# ATTiny85Shield.net
KiCad netlist of a schematic drawn in EAGLE
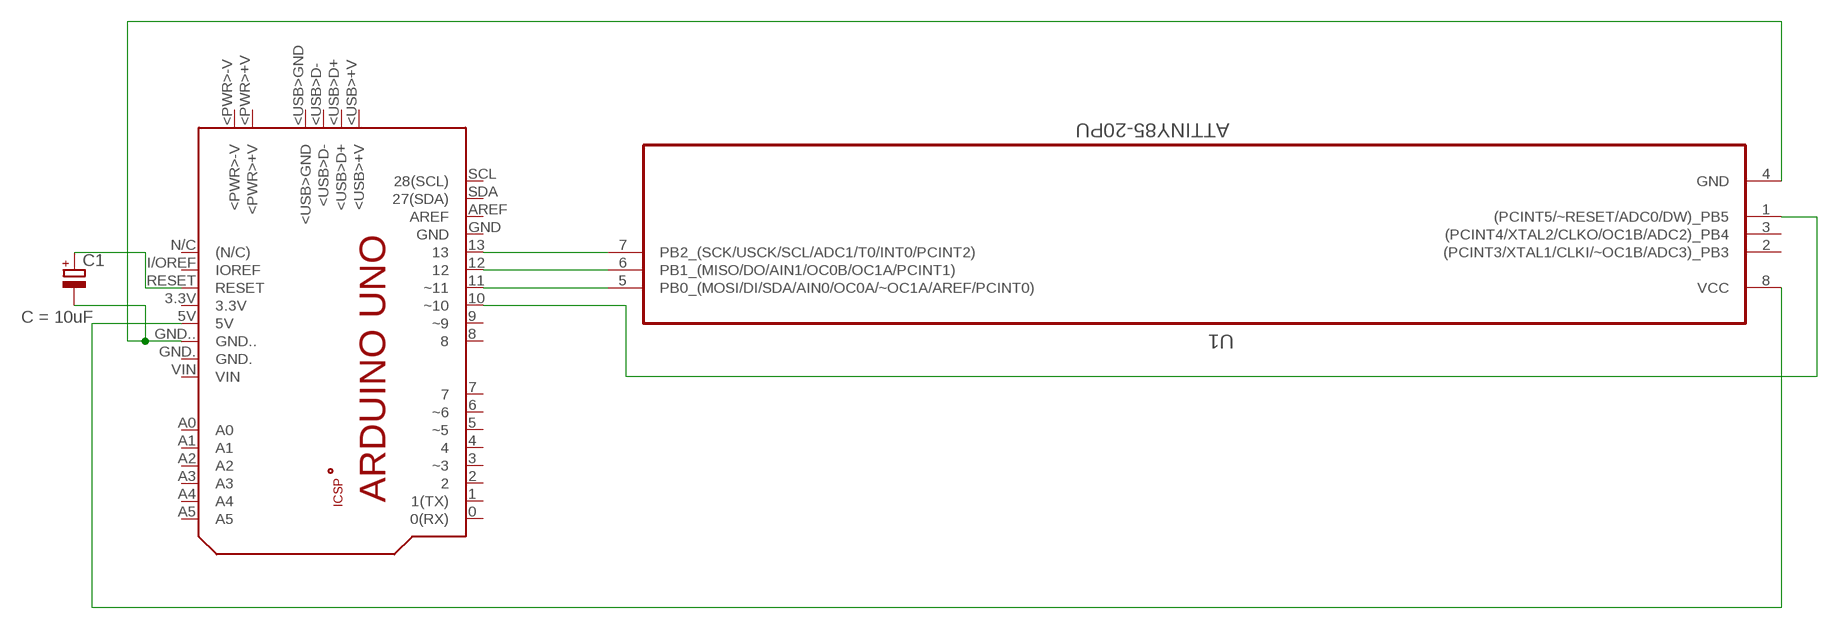
[diagram p0: schematic, sheet 1]

(export (version "E")
  (design (tool "Eeschema 10.0.6"))
  (components
    (comp (ref "C1")
      (value "CPOL-EUE3.5-8")
      (footprint "eagle-import:E3,5-8")
      (fields (field (name "C") "10uF"))
      (libsource (lib "eagle-import") (part "CPOL-EUE3.5-8"))
    )
    (comp (ref "PCB1")
      (value "ARDUINO_UNO")
      (footprint "eagle-import:ARDUINO_UNO")
      (libsource (lib "eagle-import") (part "ARDUINO_UNO"))
    )
    (comp (ref "U1")
      (value "ATTINY85-20PU")
      (footprint "eagle-import:DIP254P762X533-8")
      (libsource (lib "eagle-import") (part "ATTINY85-20PU"))
    )
  )
  (nets
    (net (code "1") (name "Net-(C1-Pad+)") (class "Default")
      (node (ref "C1") (pin "+") (pinfunction "+_+") (pintype "passive"))
      (node (ref "PCB1") (pin "RESET") (pinfunction "RESET_RESET") (pintype "bidirectional"))
    )
    (net (code "2") (name "Net-(PCB1-~{10})") (class "Default")
      (node (ref "PCB1") (pin "10") (pinfunction "~{10}_10") (pintype "bidirectional"))
      (node (ref "U1") (pin "1") (pinfunction "(PCINT5/~{RESET/ADC0/DW})_PB5_1") (pintype "bidirectional"))
    )
    (net (code "3") (name "Net-(PCB1-~{11})") (class "Default")
      (node (ref "PCB1") (pin "11") (pinfunction "~{11}_11") (pintype "bidirectional"))
      (node (ref "U1") (pin "5") (pinfunction "PB0_(MOSI/DI/SDA/AIN0/OC0A/~{OC1A/AREF/PCINT0})_5") (pintype "bidirectional"))
    )
    (net (code "4") (name "Net-(U1-GND)") (class "Default")
      (node (ref "C1") (pin "-") (pinfunction "-_-") (pintype "passive"))
      (node (ref "PCB1") (pin "GND..") (pinfunction "GND.._GND..") (pintype "bidirectional"))
      (node (ref "U1") (pin "4") (pinfunction "GND_4") (pintype "passive"))
    )
    (net (code "5") (name "Net-(U1-PB1_(MISO{slash}DO{slash}AIN1{slash}OC0B{slash}OC1A{slash}PCINT1))") (class "Default")
      (node (ref "PCB1") (pin "12") (pinfunction "12_12") (pintype "bidirectional"))
      (node (ref "U1") (pin "6") (pinfunction "PB1_(MISO/DO/AIN1/OC0B/OC1A/PCINT1)_6") (pintype "bidirectional"))
    )
    (net (code "6") (name "Net-(U1-PB2_(SCK{slash}USCK{slash}SCL{slash}ADC1{slash}T0{slash}INT0{slash}PCINT2))") (class "Default")
      (node (ref "PCB1") (pin "13") (pinfunction "13_13") (pintype "bidirectional"))
      (node (ref "U1") (pin "7") (pinfunction "PB2_(SCK/USCK/SCL/ADC1/T0/INT0/PCINT2)_7") (pintype "bidirectional"))
    )
    (net (code "7") (name "Net-(U1-VCC)") (class "Default")
      (node (ref "PCB1") (pin "5V") (pinfunction "5V_5V") (pintype "bidirectional"))
      (node (ref "U1") (pin "8") (pinfunction "VCC_8") (pintype "power_in"))
    )
    (net (code "8") (name "unconnected-(PCB1-(N{slash}C)-PadN{slash}C)") (class "Default")
      (node (ref "PCB1") (pin "N/C") (pinfunction "(N/C)_N/C") (pintype "bidirectional"))
    )
    (net (code "9") (name "unconnected-(PCB1-0(RX)-Pad0)") (class "Default")
      (node (ref "PCB1") (pin "0") (pinfunction "0(RX)_0") (pintype "bidirectional"))
    )
    (net (code "10") (name "unconnected-(PCB1-1(TX)-Pad1)") (class "Default")
      (node (ref "PCB1") (pin "1") (pinfunction "1(TX)_1") (pintype "bidirectional"))
    )
    (net (code "11") (name "unconnected-(PCB1-27(SDA)-PadSDA)") (class "Default")
      (node (ref "PCB1") (pin "SDA") (pinfunction "27(SDA)_SDA") (pintype "bidirectional"))
    )
    (net (code "12") (name "unconnected-(PCB1-28(SCL)-PadSCL)") (class "Default")
      (node (ref "PCB1") (pin "SCL") (pinfunction "28(SCL)_SCL") (pintype "bidirectional"))
    )
    (net (code "13") (name "unconnected-(PCB1-IOREF-PadI{slash}OREF)") (class "Default")
      (node (ref "PCB1") (pin "I/OREF") (pinfunction "IOREF_I/OREF") (pintype "bidirectional"))
    )
    (net (code "14") (name "unconnected-(PCB1-Pad+5V)") (class "Default")
      (node (ref "PCB1") (pin "+5V") (pinfunction "+5V_+5V") (pintype "bidirectional"))
    )
    (net (code "15") (name "unconnected-(PCB1-Pad2)") (class "Default")
      (node (ref "PCB1") (pin "2") (pinfunction "2_2") (pintype "bidirectional"))
    )
    (net (code "16") (name "unconnected-(PCB1-Pad3.3V)") (class "Default")
      (node (ref "PCB1") (pin "3.3V") (pinfunction "3.3V_3.3V") (pintype "bidirectional"))
    )
    (net (code "17") (name "unconnected-(PCB1-Pad4)") (class "Default")
      (node (ref "PCB1") (pin "4") (pinfunction "4_4") (pintype "bidirectional"))
    )
    (net (code "18") (name "unconnected-(PCB1-Pad7)") (class "Default")
      (node (ref "PCB1") (pin "7") (pinfunction "7_7") (pintype "bidirectional"))
    )
    (net (code "19") (name "unconnected-(PCB1-Pad8)") (class "Default")
      (node (ref "PCB1") (pin "8") (pinfunction "8_8") (pintype "bidirectional"))
    )
    (net (code "20") (name "unconnected-(PCB1-Pad<PWR>+V)") (class "Default")
      (node (ref "PCB1") (pin "<PWR>+V") (pinfunction "<PWR>+V_<PWR>+V") (pintype "bidirectional"))
    )
    (net (code "21") (name "unconnected-(PCB1-Pad<PWR>-V)") (class "Default")
      (node (ref "PCB1") (pin "<PWR>-V") (pinfunction "<PWR>-V_<PWR>-V") (pintype "bidirectional"))
    )
    (net (code "22") (name "unconnected-(PCB1-Pad<USB>+V)") (class "Default")
      (node (ref "PCB1") (pin "<USB>+V") (pinfunction "<USB>+V_<USB>+V") (pintype "bidirectional"))
    )
    (net (code "23") (name "unconnected-(PCB1-Pad<USB>D+)") (class "Default")
      (node (ref "PCB1") (pin "<USB>D+") (pinfunction "<USB>D+_<USB>D+") (pintype "bidirectional"))
    )
    (net (code "24") (name "unconnected-(PCB1-Pad<USB>D-)") (class "Default")
      (node (ref "PCB1") (pin "<USB>D-") (pinfunction "<USB>D-_<USB>D-") (pintype "bidirectional"))
    )
    (net (code "25") (name "unconnected-(PCB1-Pad<USB>GND)") (class "Default")
      (node (ref "PCB1") (pin "<USB>GND") (pinfunction "<USB>GND_<USB>GND") (pintype "bidirectional"))
    )
    (net (code "26") (name "unconnected-(PCB1-PadA0)") (class "Default")
      (node (ref "PCB1") (pin "A0") (pinfunction "A0_A0") (pintype "bidirectional"))
    )
    (net (code "27") (name "unconnected-(PCB1-PadA1)") (class "Default")
      (node (ref "PCB1") (pin "A1") (pinfunction "A1_A1") (pintype "bidirectional"))
    )
    (net (code "28") (name "unconnected-(PCB1-PadA2)") (class "Default")
      (node (ref "PCB1") (pin "A2") (pinfunction "A2_A2") (pintype "bidirectional"))
    )
    (net (code "29") (name "unconnected-(PCB1-PadA3)") (class "Default")
      (node (ref "PCB1") (pin "A3") (pinfunction "A3_A3") (pintype "bidirectional"))
    )
    (net (code "30") (name "unconnected-(PCB1-PadA4)") (class "Default")
      (node (ref "PCB1") (pin "A4") (pinfunction "A4_A4") (pintype "bidirectional"))
    )
    (net (code "31") (name "unconnected-(PCB1-PadA5)") (class "Default")
      (node (ref "PCB1") (pin "A5") (pinfunction "A5_A5") (pintype "bidirectional"))
    )
    (net (code "32") (name "unconnected-(PCB1-PadAREF)") (class "Default")
      (node (ref "PCB1") (pin "AREF") (pinfunction "AREF_AREF") (pintype "bidirectional"))
    )
    (net (code "33") (name "unconnected-(PCB1-PadGND)") (class "Default")
      (node (ref "PCB1") (pin "GND") (pinfunction "GND_GND") (pintype "bidirectional"))
    )
    (net (code "34") (name "unconnected-(PCB1-PadGND.)") (class "Default")
      (node (ref "PCB1") (pin "GND.") (pinfunction "GND._GND.") (pintype "bidirectional"))
    )
    (net (code "35") (name "unconnected-(PCB1-PadGND_)") (class "Default")
      (node (ref "PCB1") (pin "GND_") (pinfunction "GND__GND_") (pintype "bidirectional"))
    )
    (net (code "36") (name "unconnected-(PCB1-PadMISO)") (class "Default")
      (node (ref "PCB1") (pin "MISO") (pinfunction "MISO_MISO") (pintype "bidirectional"))
    )
    (net (code "37") (name "unconnected-(PCB1-PadMOSI)") (class "Default")
      (node (ref "PCB1") (pin "MOSI") (pinfunction "MOSI_MOSI") (pintype "bidirectional"))
    )
    (net (code "38") (name "unconnected-(PCB1-PadRESET.)") (class "Default")
      (node (ref "PCB1") (pin "RESET.") (pinfunction "RESET._RESET.") (pintype "bidirectional"))
    )
    (net (code "39") (name "unconnected-(PCB1-PadSCK)") (class "Default")
      (node (ref "PCB1") (pin "SCK") (pinfunction "SCK_SCK") (pintype "bidirectional"))
    )
    (net (code "40") (name "unconnected-(PCB1-PadVIN)") (class "Default")
      (node (ref "PCB1") (pin "VIN") (pinfunction "VIN_VIN") (pintype "bidirectional"))
    )
    (net (code "41") (name "unconnected-(PCB1-~{3}-Pad3)") (class "Default")
      (node (ref "PCB1") (pin "3") (pinfunction "~{3}_3") (pintype "bidirectional"))
    )
    (net (code "42") (name "unconnected-(PCB1-~{5}-Pad5)") (class "Default")
      (node (ref "PCB1") (pin "5") (pinfunction "~{5}_5") (pintype "bidirectional"))
    )
    (net (code "43") (name "unconnected-(PCB1-~{6}-Pad6)") (class "Default")
      (node (ref "PCB1") (pin "6") (pinfunction "~{6}_6") (pintype "bidirectional"))
    )
    (net (code "44") (name "unconnected-(PCB1-~{9}-Pad9)") (class "Default")
      (node (ref "PCB1") (pin "9") (pinfunction "~{9}_9") (pintype "bidirectional"))
    )
    (net (code "45") (name "unconnected-(U1-(PCINT3{slash}XTAL1{slash}CLKI{slash}~{OC1B{slash}ADC3})_PB3-Pad2)") (class "Default")
      (node (ref "U1") (pin "2") (pinfunction "(PCINT3/XTAL1/CLKI/~{OC1B/ADC3})_PB3_2") (pintype "bidirectional"))
    )
    (net (code "46") (name "unconnected-(U1-(PCINT4{slash}XTAL2{slash}CLKO{slash}OC1B{slash}ADC2)_PB4-Pad3)") (class "Default")
      (node (ref "U1") (pin "3") (pinfunction "(PCINT4/XTAL2/CLKO/OC1B/ADC2)_PB4_3") (pintype "bidirectional"))
    )
  )
)
